# E1811SENSE_1.net
KiCad netlist of a schematic drawn in Altium Designer
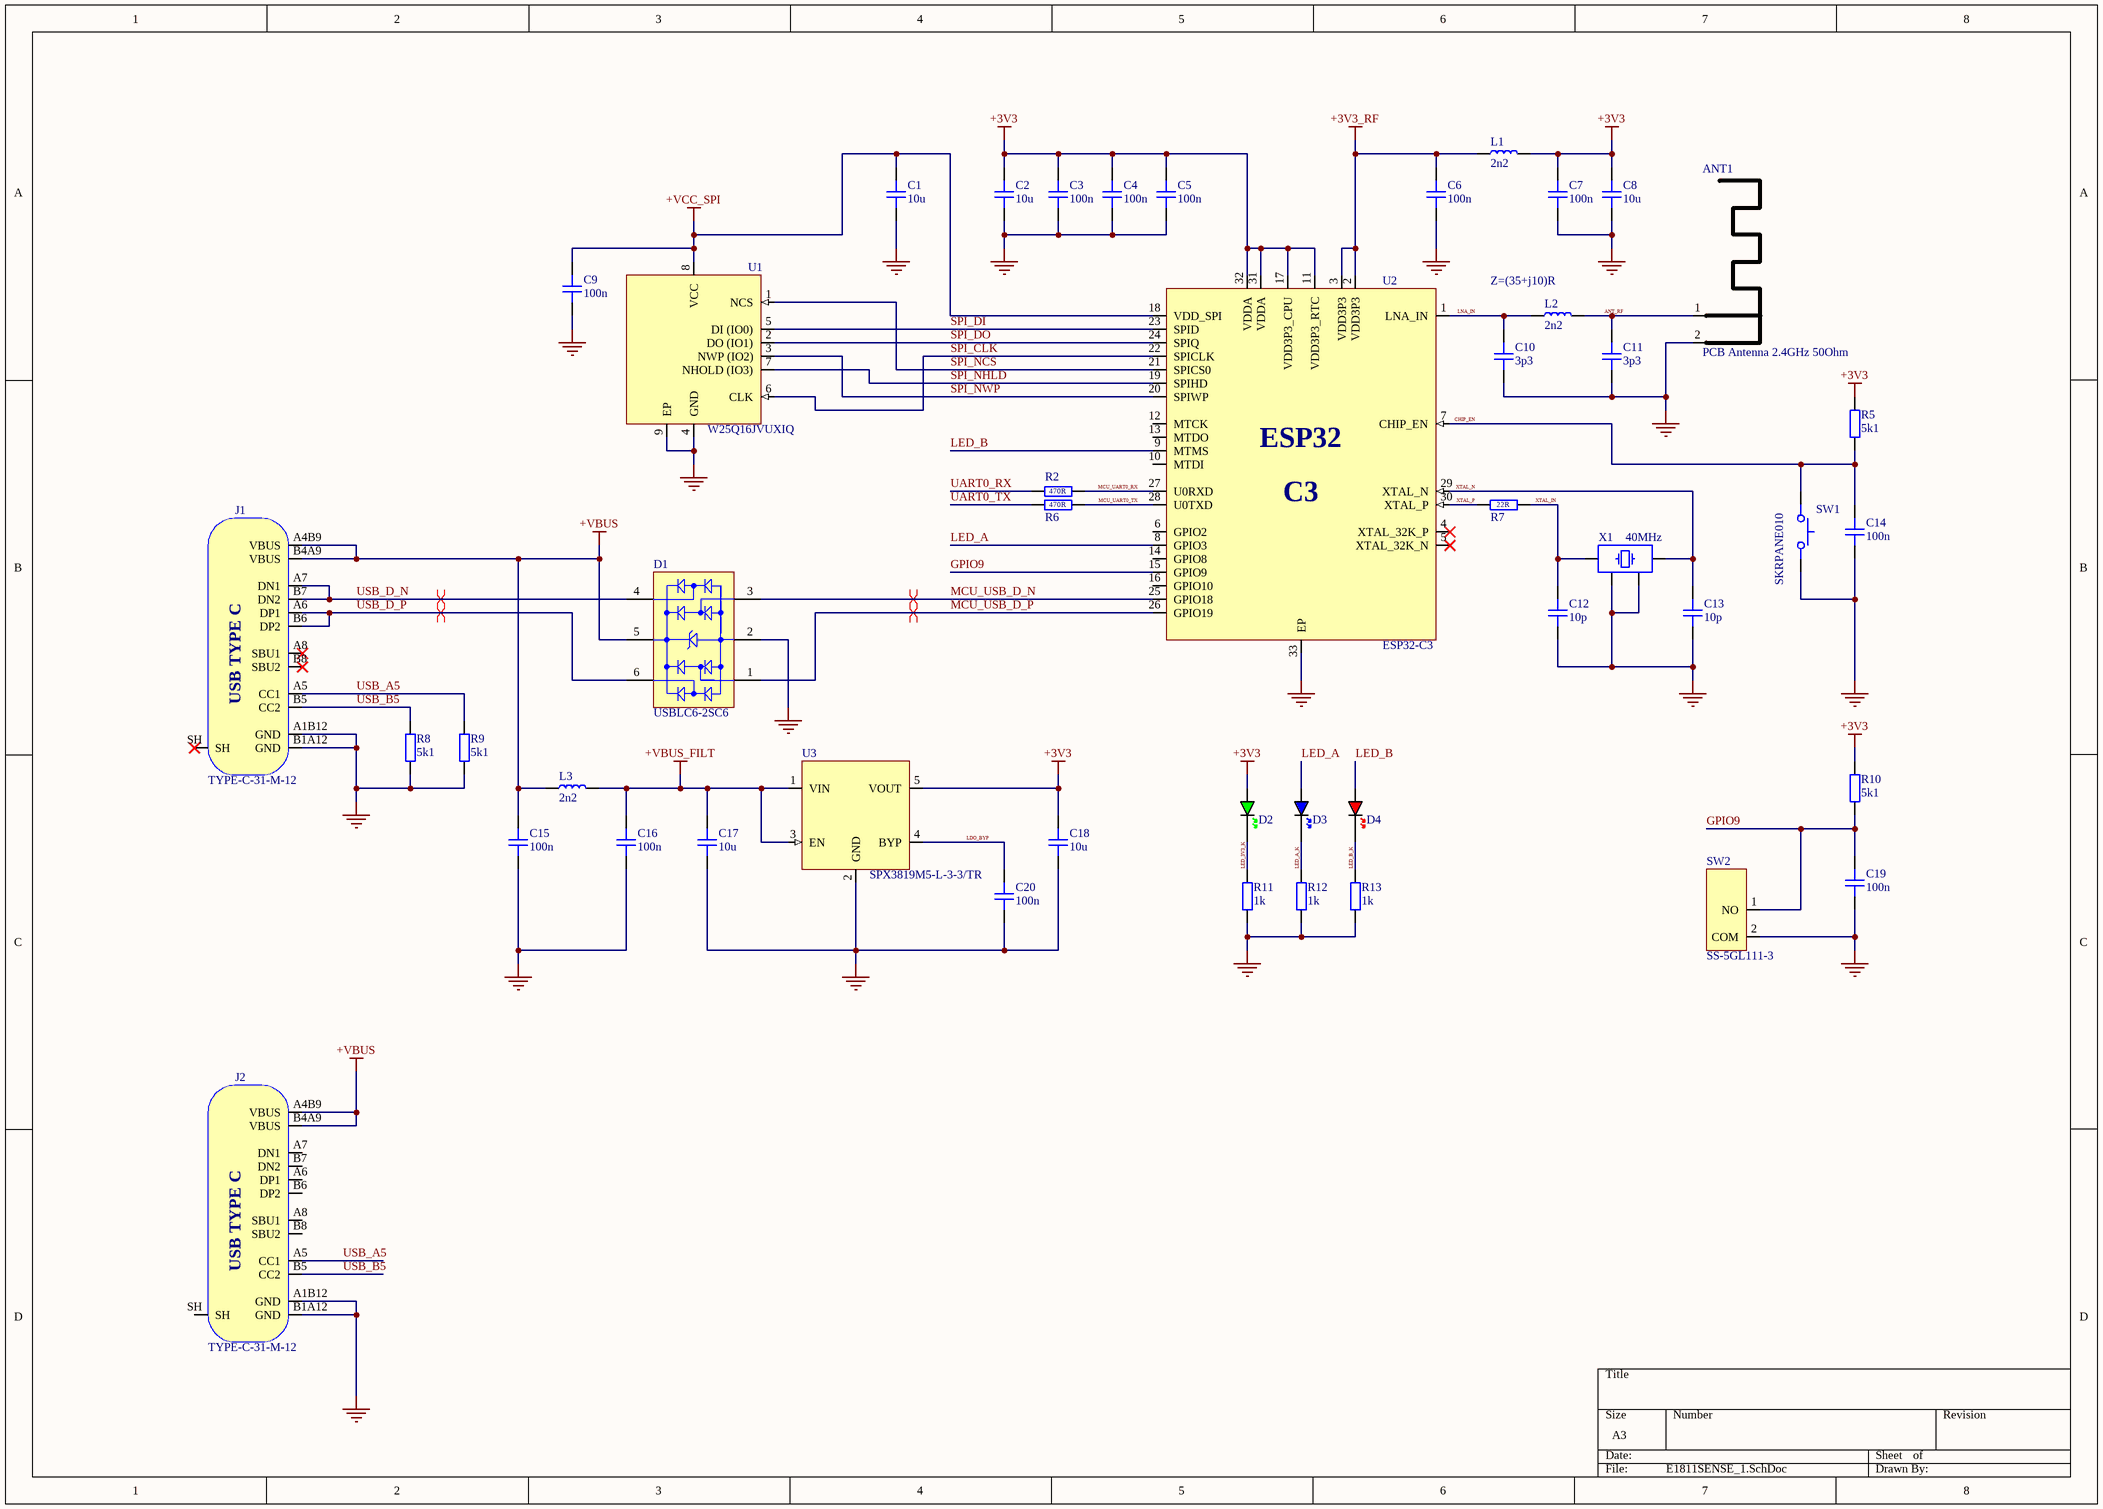
[diagram p0: E1811SENSE_1.SchDoc]

(export (version "E")
  (design (tool "Eeschema 10.0.6"))
  (components
    (comp (ref "ANT1")
      (value "PCB Antenna 2.4GHz 50Ohm")
      (footprint "ANT_IFA_USB_2_4GHZ_50R")
      (description "Inverted F 2.4GHz ISM PCB Antenna 50 Ohm")
      (libsource (lib "Schematic-Lib-PhilsLab") (part "ANT_IFA_USB_2_4GHZ_50R"))
    )
    (comp (ref "C1")
      (value "10u")
      (footprint "CAP_0603")
      (description "Capacitor SMD 0603 10V")
      (fields
        (field (name "MANUFACTURER") "Samsung")
        (field (name "MANUFACTURER PART NUMBER") "CL10A106KP8NNNC")
      )
      (libsource (lib "Schematic-Lib-PhilsLab") (part "CAP_0603_10V"))
    )
    (comp (ref "C2")
      (value "10u")
      (footprint "CAP_0603")
      (description "Capacitor SMD 0603 10V")
      (fields
        (field (name "MANUFACTURER") "Samsung")
        (field (name "MANUFACTURER PART NUMBER") "CL10A106KP8NNNC")
      )
      (libsource (lib "Schematic-Lib-PhilsLab") (part "CAP_0603_10V"))
    )
    (comp (ref "C3")
      (value "100n")
      (footprint "CAP_0402")
      (description "Capacitor SMD 0402 50V")
      (fields
        (field (name "MANUFACTURER") "Samsung")
        (field (name "MANUFACTURER PART NUMBER") "CL05B104KO5NNNC")
      )
      (libsource (lib "Schematic-Lib-PhilsLab") (part "CAP_0402_50V"))
    )
    (comp (ref "C4")
      (value "100n")
      (footprint "CAP_0402")
      (description "Capacitor SMD 0402 50V")
      (fields
        (field (name "MANUFACTURER") "Samsung")
        (field (name "MANUFACTURER PART NUMBER") "CL05B104KO5NNNC")
      )
      (libsource (lib "Schematic-Lib-PhilsLab") (part "CAP_0402_50V"))
    )
    (comp (ref "C5")
      (value "100n")
      (footprint "CAP_0402")
      (description "Capacitor SMD 0402 50V")
      (fields
        (field (name "MANUFACTURER") "Samsung")
        (field (name "MANUFACTURER PART NUMBER") "CL05B104KO5NNNC")
      )
      (libsource (lib "Schematic-Lib-PhilsLab") (part "CAP_0402_50V"))
    )
    (comp (ref "C6")
      (value "100n")
      (footprint "CAP_0402")
      (description "Capacitor SMD 0402 50V")
      (fields
        (field (name "MANUFACTURER") "Samsung")
        (field (name "MANUFACTURER PART NUMBER") "CL05B104KO5NNNC")
      )
      (libsource (lib "Schematic-Lib-PhilsLab") (part "CAP_0402_50V"))
    )
    (comp (ref "C7")
      (value "100n")
      (footprint "CAP_0402")
      (description "Capacitor SMD 0402 50V")
      (fields
        (field (name "MANUFACTURER") "Samsung")
        (field (name "MANUFACTURER PART NUMBER") "CL05B104KO5NNNC")
      )
      (libsource (lib "Schematic-Lib-PhilsLab") (part "CAP_0402_50V"))
    )
    (comp (ref "C8")
      (value "10u")
      (footprint "CAP_0603")
      (description "Capacitor SMD 0603 10V")
      (fields
        (field (name "MANUFACTURER") "Samsung")
        (field (name "MANUFACTURER PART NUMBER") "CL10A106KP8NNNC")
      )
      (libsource (lib "Schematic-Lib-PhilsLab") (part "CAP_0603_10V"))
    )
    (comp (ref "C9")
      (value "100n")
      (footprint "CAP_0402")
      (description "Capacitor SMD 0402 50V")
      (fields
        (field (name "MANUFACTURER") "Samsung")
        (field (name "MANUFACTURER PART NUMBER") "CL05B104KO5NNNC")
      )
      (libsource (lib "Schematic-Lib-PhilsLab") (part "CAP_0402_50V"))
    )
    (comp (ref "C10")
      (value "3p3")
      (footprint "CAP_0402")
      (description "Capacitor SMD 0402 50V")
      (fields (field (name "MANUFACTURER") "FH") (field (name "MANUFACTURER PART NUMBER") "0402CG3R3C500NT"))
      (libsource (lib "Schematic-Lib-PhilsLab") (part "CAP_0402_50V"))
    )
    (comp (ref "C11")
      (value "3p3")
      (footprint "CAP_0402")
      (description "Capacitor SMD 0402 50V")
      (fields (field (name "MANUFACTURER") "FH") (field (name "MANUFACTURER PART NUMBER") "0402CG3R3C500NT"))
      (libsource (lib "Schematic-Lib-PhilsLab") (part "CAP_0402_50V"))
    )
    (comp (ref "C12")
      (value "10p")
      (footprint "CAP_0402")
      (description "Capacitor SMD 0402 50V")
      (fields
        (field (name "MANUFACTURER") "Samsung")
        (field (name "MANUFACTURER PART NUMBER") "CL05C100JB5NNNC")
      )
      (libsource (lib "Schematic-Lib-PhilsLab") (part "CAP_0402_50V"))
    )
    (comp (ref "C13")
      (value "10p")
      (footprint "CAP_0402")
      (description "Capacitor SMD 0402 50V")
      (fields
        (field (name "MANUFACTURER") "Samsung")
        (field (name "MANUFACTURER PART NUMBER") "CL05C100JB5NNNC")
      )
      (libsource (lib "Schematic-Lib-PhilsLab") (part "CAP_0402_50V"))
    )
    (comp (ref "C14")
      (value "100n")
      (footprint "CAP_0402")
      (description "Capacitor SMD 0402 50V")
      (fields
        (field (name "MANUFACTURER") "Samsung")
        (field (name "MANUFACTURER PART NUMBER") "CL05B104KO5NNNC")
      )
      (libsource (lib "Schematic-Lib-PhilsLab") (part "CAP_0402_50V"))
    )
    (comp (ref "C15")
      (value "100n")
      (footprint "CAP_0402")
      (description "Capacitor SMD 0402 50V")
      (fields
        (field (name "MANUFACTURER") "Samsung")
        (field (name "MANUFACTURER PART NUMBER") "CL05B104KO5NNNC")
      )
      (libsource (lib "Schematic-Lib-PhilsLab") (part "CAP_0402_50V"))
    )
    (comp (ref "C16")
      (value "100n")
      (footprint "CAP_0402")
      (description "Capacitor SMD 0402 50V")
      (fields
        (field (name "MANUFACTURER") "Samsung")
        (field (name "MANUFACTURER PART NUMBER") "CL05B104KO5NNNC")
      )
      (libsource (lib "Schematic-Lib-PhilsLab") (part "CAP_0402_50V"))
    )
    (comp (ref "C17")
      (value "10u")
      (footprint "CAP_0603")
      (description "Capacitor SMD 0603 10V")
      (fields
        (field (name "MANUFACTURER") "Samsung")
        (field (name "MANUFACTURER PART NUMBER") "CL10A106KP8NNNC")
      )
      (libsource (lib "Schematic-Lib-PhilsLab") (part "CAP_0603_10V"))
    )
    (comp (ref "C18")
      (value "10u")
      (footprint "CAP_0603")
      (description "Capacitor SMD 0603 10V")
      (fields
        (field (name "MANUFACTURER") "Samsung")
        (field (name "MANUFACTURER PART NUMBER") "CL10A106KP8NNNC")
      )
      (libsource (lib "Schematic-Lib-PhilsLab") (part "CAP_0603_10V"))
    )
    (comp (ref "C19")
      (value "100n")
      (footprint "CAP_0402")
      (description "Capacitor SMD 0402 50V")
      (fields
        (field (name "MANUFACTURER") "Samsung")
        (field (name "MANUFACTURER PART NUMBER") "CL05B104KO5NNNC")
      )
      (libsource (lib "Schematic-Lib-PhilsLab") (part "CAP_0402_50V"))
    )
    (comp (ref "C20")
      (value "100n")
      (footprint "CAP_0402")
      (description "Capacitor SMD 0402 50V")
      (fields
        (field (name "MANUFACTURER") "Samsung")
        (field (name "MANUFACTURER PART NUMBER") "CL05B104KO5NNNC")
      )
      (libsource (lib "Schematic-Lib-PhilsLab") (part "CAP_0402_50V"))
    )
    (comp (ref "D1")
      (value "USBLC6-2SC6")
      (footprint "STM-SOT23-6L_V")
      (description "Very low capacitance ESD protection, 3.5 pF, -40 to 125 degC, 6-Pin SOT23, RoHS, Tape and Reel")
      (fields (field (name "MANUFACTURER") "STMicroelectronics"))
      (libsource (lib "Altium Content Vault") (part "STM-USB_DVI_HDMIULC6-4SC6X-SOT23-6L"))
    )
    (comp (ref "D2")
      (value "GREEN")
      (footprint "LED_0603_GREEN")
      (description "LED 0603 GREEN SMD")
      (libsource (lib "Schematic-Lib-PhilsLab") (part "LED_0603_GREEN"))
    )
    (comp (ref "D3")
      (value "BLUE")
      (footprint "LED_0603_BLUE")
      (description "LED 0603 BLUE SMD")
      (libsource (lib "Schematic-Lib-PhilsLab") (part "LED_0603_BLUE"))
    )
    (comp (ref "D4")
      (value "RED")
      (footprint "LED_0603_RED")
      (description "LED 0603 RED SMD")
      (libsource (lib "Schematic-Lib-PhilsLab") (part "LED_0603_RED"))
    )
    (comp (ref "J1")
      (value "TYPE-C-31-M-12")
      (footprint "TYPE-C-31-M-12")
      (description "USB Type C Connector Horizontal SMT")
      (fields (field (name "MANUFACTURER") "Koren Hroparts"))
      (libsource (lib "Schematic-Lib-PhilsLab") (part "TYPE-C-31-M-12"))
    )
    (comp (ref "J2")
      (value "TYPE-C-31-M-12")
      (footprint "TYPE-C-31-M-12")
      (description "USB Type C Connector Horizontal SMT")
      (fields (field (name "MANUFACTURER") "Koren Hroparts"))
      (libsource (lib "Schematic-Lib-PhilsLab") (part "TYPE-C-31-M-12"))
    )
    (comp (ref "L1")
      (value "2n2")
      (footprint "IND_0402")
      (description "Inductor SMD 0402")
      (fields
        (field (name "MANUFACTURER") "Murata")
        (field (name "MANUFACTURER PART NUMBER") "LQW15AN2N2G80D")
      )
      (libsource (lib "Schematic-Lib-PhilsLab") (part "IND_0402"))
    )
    (comp (ref "L2")
      (value "2n2")
      (footprint "IND_0402")
      (description "Inductor SMD 0402")
      (fields
        (field (name "MANUFACTURER") "Murata")
        (field (name "MANUFACTURER PART NUMBER") "LQW15AN2N2G80D")
      )
      (libsource (lib "Schematic-Lib-PhilsLab") (part "IND_0402"))
    )
    (comp (ref "L3")
      (value "2n2")
      (footprint "IND_0402")
      (description "Inductor SMD 0402")
      (fields
        (field (name "MANUFACTURER") "Murata")
        (field (name "MANUFACTURER PART NUMBER") "LQW15AN2N2G80D")
      )
      (libsource (lib "Schematic-Lib-PhilsLab") (part "IND_0402"))
    )
    (comp (ref "R2")
      (value "470R")
      (footprint "RES_0402")
      (description "Resistor SMD 0402")
      (fields
        (field (name "MANUFACTURER") "UNI-ROYAL")
        (field (name "MANUFACTURER PART NUMBER") "0402WGF4700TCE")
      )
      (libsource (lib "Schematic-Lib-PhilsLab") (part "RES_0402"))
    )
    (comp (ref "R5")
      (value "5k1")
      (footprint "RES_0402")
      (description "Resistor SMD 0402")
      (fields
        (field (name "MANUFACTURER") "YAGEO")
        (field (name "MANUFACTURER PART NUMBER") "RC0402JR-075K1L")
      )
      (libsource (lib "Schematic-Lib-PhilsLab") (part "RES_0402"))
    )
    (comp (ref "R6")
      (value "470R")
      (footprint "RES_0402")
      (description "Resistor SMD 0402")
      (fields
        (field (name "MANUFACTURER") "UNI-ROYAL")
        (field (name "MANUFACTURER PART NUMBER") "0402WGF4700TCE")
      )
      (libsource (lib "Schematic-Lib-PhilsLab") (part "RES_0402"))
    )
    (comp (ref "R7")
      (value "22R")
      (footprint "RES_0402")
      (description "Resistor SMD 0402")
      (fields
        (field (name "MANUFACTURER") "UNI-ROYAL")
        (field (name "MANUFACTURER PART NUMBER") "0402WGF220JTCE")
      )
      (libsource (lib "Schematic-Lib-PhilsLab") (part "RES_0402"))
    )
    (comp (ref "R8")
      (value "5k1")
      (footprint "RES_0402")
      (description "Resistor SMD 0402")
      (fields
        (field (name "MANUFACTURER") "YAGEO")
        (field (name "MANUFACTURER PART NUMBER") "RC0402JR-075K1L")
      )
      (libsource (lib "Schematic-Lib-PhilsLab") (part "RES_0402"))
    )
    (comp (ref "R9")
      (value "5k1")
      (footprint "RES_0402")
      (description "Resistor SMD 0402")
      (fields
        (field (name "MANUFACTURER") "YAGEO")
        (field (name "MANUFACTURER PART NUMBER") "RC0402JR-075K1L")
      )
      (libsource (lib "Schematic-Lib-PhilsLab") (part "RES_0402"))
    )
    (comp (ref "R10")
      (value "5k1")
      (footprint "RES_0402")
      (description "Resistor SMD 0402")
      (fields
        (field (name "MANUFACTURER") "YAGEO")
        (field (name "MANUFACTURER PART NUMBER") "RC0402JR-075K1L")
      )
      (libsource (lib "Schematic-Lib-PhilsLab") (part "RES_0402"))
    )
    (comp (ref "R11")
      (value "1k")
      (footprint "RES_0402")
      (description "Resistor SMD 0402")
      (fields
        (field (name "MANUFACTURER") "UNI-ROYAL")
        (field (name "MANUFACTURER PART NUMBER") "0402WGF4700TCE")
      )
      (libsource (lib "Schematic-Lib-PhilsLab") (part "RES_0402"))
    )
    (comp (ref "R12")
      (value "1k")
      (footprint "RES_0402")
      (description "Resistor SMD 0402")
      (fields
        (field (name "MANUFACTURER") "UNI-ROYAL")
        (field (name "MANUFACTURER PART NUMBER") "0402WGF4700TCE")
      )
      (libsource (lib "Schematic-Lib-PhilsLab") (part "RES_0402"))
    )
    (comp (ref "R13")
      (value "1k")
      (footprint "RES_0402")
      (description "Resistor SMD 0402")
      (fields
        (field (name "MANUFACTURER") "UNI-ROYAL")
        (field (name "MANUFACTURER PART NUMBER") "0402WGF4700TCE")
      )
      (libsource (lib "Schematic-Lib-PhilsLab") (part "RES_0402"))
    )
    (comp (ref "SW1")
      (value "SKRPANE010")
      (footprint "SKRPANE010")
      (description "Tactile Switch SMD SPST")
      (fields (field (name "MANUFACTURER") "Alps Alpine"))
      (libsource (lib "Schematic-Lib-PhilsLab") (part "SKRPANE010"))
    )
    (comp (ref "SW2")
      (value "SS-5GL111-3")
      (footprint "SS-5GL1131-3")
      (libsource (lib "SchLibrary") (part "SS-5GL111-3"))
    )
    (comp (ref "U1")
      (value "W25Q16JVUXIQ")
      (footprint "USON-8-2X3MM")
      (description "16M-BIT SERIAL FLASH MEMORY WITH\r\nDUAL/QUAD SPI USON-8")
      (fields (field (name "MANUFACTURER") "Winbond"))
      (libsource (lib "Schematic-Lib-PhilsLab") (part "W25Q16JVUXIQ"))
    )
    (comp (ref "U2")
      (value "ESP32-C3")
      (footprint "QFN32-5x5")
      (fields (field (name "MANUFACTURER") "Espressif"))
      (libsource (lib "Schematic-Lib-PhilsLab") (part "ESP32-C3"))
    )
    (comp (ref "U3")
      (value "SPX3819M5-L-3-3/TR")
      (footprint "SOT-23-5")
      (description "500mA +3.3V Low-Noise LDO Voltage Regulator")
      (fields (field (name "MANUFACTURER") "MaxLinear"))
      (libsource (lib "Schematic-Lib-PhilsLab") (part "SPX3819M5-L-3-3/TR"))
    )
    (comp (ref "X1")
      (value "40MHz")
      (footprint "XTAL_2520")
      (description "Crystal SMD 2520")
      (fields (field (name "MANUFACTURER") "Seiko Epson"))
      (libsource (lib "Schematic-Lib-PhilsLab") (part "XTAL_2520"))
    )
  )
  (nets
    (net (code "1") (name "+3V3") (class "Default")
      (node (ref "C18") (pin "2") (pinfunction "2_2") (pintype "passive"))
      (node (ref "C2") (pin "2") (pinfunction "2_2") (pintype "passive"))
      (node (ref "C3") (pin "2") (pinfunction "2_2") (pintype "passive"))
      (node (ref "C4") (pin "2") (pinfunction "2_2") (pintype "passive"))
      (node (ref "C5") (pin "2") (pinfunction "2_2") (pintype "passive"))
      (node (ref "C7") (pin "2") (pinfunction "2_2") (pintype "passive"))
      (node (ref "C8") (pin "2") (pinfunction "2_2") (pintype "passive"))
      (node (ref "D2") (pin "A") (pinfunction "A_A") (pintype "passive"))
      (node (ref "L1") (pin "1") (pinfunction "1_1") (pintype "passive"))
      (node (ref "R10") (pin "2") (pinfunction "2_2") (pintype "passive"))
      (node (ref "R5") (pin "2") (pinfunction "2_2") (pintype "passive"))
      (node (ref "U2") (pin "11") (pinfunction "VDD3P3_RTC_11") (pintype "power_in"))
      (node (ref "U2") (pin "17") (pinfunction "VDD3P3_CPU_17") (pintype "power_in"))
      (node (ref "U2") (pin "31") (pinfunction "VDDA_31") (pintype "power_in"))
      (node (ref "U2") (pin "32") (pinfunction "VDDA_32") (pintype "power_in"))
      (node (ref "U3") (pin "5") (pinfunction "VOUT_5") (pintype "power_in"))
    )
    (net (code "2") (name "+3V3_RF") (class "Default")
      (node (ref "C6") (pin "2") (pinfunction "2_2") (pintype "passive"))
      (node (ref "L1") (pin "2") (pinfunction "2_2") (pintype "passive"))
      (node (ref "U2") (pin "2") (pinfunction "VDD3P3_2") (pintype "power_in"))
      (node (ref "U2") (pin "3") (pinfunction "VDD3P3_3") (pintype "power_in"))
    )
    (net (code "3") (name "+VBUS") (class "Default")
      (node (ref "C15") (pin "2") (pinfunction "2_2") (pintype "passive"))
      (node (ref "D1") (pin "5") (pinfunction "VBUS_5") (pintype "passive"))
      (node (ref "J1") (pin "A4B9") (pinfunction "VBUS_A4B9") (pintype "power_in"))
      (node (ref "J1") (pin "B4A9") (pinfunction "VBUS_B4A9") (pintype "power_in"))
      (node (ref "J2") (pin "A4B9") (pinfunction "VBUS_A4B9") (pintype "power_in"))
      (node (ref "J2") (pin "B4A9") (pinfunction "VBUS_B4A9") (pintype "power_in"))
      (node (ref "L3") (pin "2") (pinfunction "2_2") (pintype "passive"))
    )
    (net (code "4") (name "+VBUS_FILT") (class "Default")
      (node (ref "C16") (pin "2") (pinfunction "2_2") (pintype "passive"))
      (node (ref "C17") (pin "2") (pinfunction "2_2") (pintype "passive"))
      (node (ref "L3") (pin "1") (pinfunction "1_1") (pintype "passive"))
      (node (ref "U3") (pin "1") (pinfunction "VIN_1") (pintype "power_in"))
      (node (ref "U3") (pin "3") (pinfunction "EN_3") (pintype "input"))
    )
    (net (code "5") (name "+VCC_SPI") (class "Default")
      (node (ref "C1") (pin "2") (pinfunction "2_2") (pintype "passive"))
      (node (ref "C9") (pin "2") (pinfunction "2_2") (pintype "passive"))
      (node (ref "U1") (pin "8") (pinfunction "VCC_8") (pintype "power_in"))
      (node (ref "U2") (pin "18") (pinfunction "VDD_SPI_18") (pintype "power_in"))
    )
    (net (code "6") (name "/ANT_RF") (class "Default")
      (node (ref "ANT1") (pin "1") (pinfunction "RF_1") (pintype "passive"))
      (node (ref "C11") (pin "2") (pinfunction "2_2") (pintype "passive"))
      (node (ref "L2") (pin "1") (pinfunction "1_1") (pintype "passive"))
    )
    (net (code "7") (name "/CHIP_EN") (class "Default")
      (node (ref "C14") (pin "2") (pinfunction "2_2") (pintype "passive"))
      (node (ref "R5") (pin "1") (pinfunction "1_1") (pintype "passive"))
      (node (ref "SW1") (pin "34") (pintype "passive"))
      (node (ref "U2") (pin "7") (pinfunction "CHIP_EN_7") (pintype "input"))
    )
    (net (code "8") (name "/GPIO9") (class "Default")
      (node (ref "C19") (pin "2") (pinfunction "2_2") (pintype "passive"))
      (node (ref "R10") (pin "1") (pinfunction "1_1") (pintype "passive"))
      (node (ref "SW2") (pin "1") (pinfunction "NO_1") (pintype "passive"))
      (node (ref "U2") (pin "15") (pinfunction "GPIO9_15") (pintype "bidirectional"))
    )
    (net (code "9") (name "/LDO_BYP") (class "Default")
      (node (ref "C20") (pin "2") (pinfunction "2_2") (pintype "passive"))
      (node (ref "U3") (pin "4") (pinfunction "BYP_4") (pintype "passive"))
    )
    (net (code "10") (name "/LED_3V3_K") (class "Default")
      (node (ref "D2") (pin "K") (pinfunction "K_K") (pintype "passive"))
      (node (ref "R11") (pin "2") (pinfunction "2_2") (pintype "passive"))
    )
    (net (code "11") (name "/LED_A") (class "Default")
      (node (ref "D3") (pin "A") (pinfunction "A_A") (pintype "passive"))
      (node (ref "U2") (pin "8") (pinfunction "GPIO3_8") (pintype "bidirectional"))
    )
    (net (code "12") (name "/LED_A_K") (class "Default")
      (node (ref "D3") (pin "K") (pinfunction "K_K") (pintype "passive"))
      (node (ref "R12") (pin "2") (pinfunction "2_2") (pintype "passive"))
    )
    (net (code "13") (name "/LED_B") (class "Default")
      (node (ref "D4") (pin "A") (pinfunction "A_A") (pintype "passive"))
      (node (ref "U2") (pin "9") (pinfunction "MTMS_9") (pintype "bidirectional"))
    )
    (net (code "14") (name "/LED_B_K") (class "Default")
      (node (ref "D4") (pin "K") (pinfunction "K_K") (pintype "passive"))
      (node (ref "R13") (pin "2") (pinfunction "2_2") (pintype "passive"))
    )
    (net (code "15") (name "/LNA_IN") (class "Default")
      (node (ref "C10") (pin "2") (pinfunction "2_2") (pintype "passive"))
      (node (ref "L2") (pin "2") (pinfunction "2_2") (pintype "passive"))
      (node (ref "U2") (pin "1") (pinfunction "LNA_IN_1") (pintype "bidirectional"))
    )
    (net (code "16") (name "/MCU_UART0_RX") (class "Default")
      (node (ref "R2") (pin "2") (pinfunction "2_2") (pintype "passive"))
      (node (ref "U2") (pin "27") (pinfunction "U0RXD_27") (pintype "bidirectional"))
    )
    (net (code "17") (name "/MCU_UART0_TX") (class "Default")
      (node (ref "R6") (pin "2") (pinfunction "2_2") (pintype "passive"))
      (node (ref "U2") (pin "28") (pinfunction "U0TXD_28") (pintype "bidirectional"))
    )
    (net (code "18") (name "/MCU_USB_D_N") (class "Default")
      (node (ref "D1") (pin "3") (pinfunction "I/O_2_3") (pintype "passive"))
      (node (ref "U2") (pin "25") (pinfunction "GPIO18_25") (pintype "bidirectional"))
    )
    (net (code "19") (name "/MCU_USB_D_P") (class "Default")
      (node (ref "D1") (pin "1") (pinfunction "I/O_1_1") (pintype "passive"))
      (node (ref "U2") (pin "26") (pinfunction "GPIO19_26") (pintype "bidirectional"))
    )
    (net (code "20") (name "/SPI_CLK") (class "Default")
      (node (ref "U1") (pin "6") (pinfunction "CLK_6") (pintype "input"))
      (node (ref "U2") (pin "22") (pinfunction "SPICLK_22") (pintype "bidirectional"))
    )
    (net (code "21") (name "/SPI_DI") (class "Default")
      (node (ref "U1") (pin "5") (pinfunction "DI_(IO0)_5") (pintype "bidirectional"))
      (node (ref "U2") (pin "23") (pinfunction "SPID_23") (pintype "bidirectional"))
    )
    (net (code "22") (name "/SPI_DO") (class "Default")
      (node (ref "U1") (pin "2") (pinfunction "DO_(IO1)_2") (pintype "bidirectional"))
      (node (ref "U2") (pin "24") (pinfunction "SPIQ_24") (pintype "bidirectional"))
    )
    (net (code "23") (name "/SPI_NCS") (class "Default")
      (node (ref "U1") (pin "1") (pinfunction "NCS_1") (pintype "input"))
      (node (ref "U2") (pin "21") (pinfunction "SPICS0_21") (pintype "bidirectional"))
    )
    (net (code "24") (name "/SPI_NHLD") (class "Default")
      (node (ref "U1") (pin "7") (pinfunction "NHOLD_(IO3)_7") (pintype "bidirectional"))
      (node (ref "U2") (pin "19") (pinfunction "SPIHD_19") (pintype "bidirectional"))
    )
    (net (code "25") (name "/SPI_NWP") (class "Default")
      (node (ref "U1") (pin "3") (pinfunction "NWP_(IO2)_3") (pintype "bidirectional"))
      (node (ref "U2") (pin "20") (pinfunction "SPIWP_20") (pintype "bidirectional"))
    )
    (net (code "26") (name "/UART0_RX") (class "Default")
      (node (ref "R2") (pin "1") (pinfunction "1_1") (pintype "passive"))
    )
    (net (code "27") (name "/UART0_TX") (class "Default")
      (node (ref "R6") (pin "1") (pinfunction "1_1") (pintype "passive"))
    )
    (net (code "28") (name "/USB_A5") (class "Default")
      (node (ref "J1") (pin "A5") (pinfunction "CC1_A5") (pintype "passive"))
      (node (ref "J2") (pin "A5") (pinfunction "CC1_A5") (pintype "passive"))
      (node (ref "R9") (pin "1") (pinfunction "1_1") (pintype "passive"))
    )
    (net (code "29") (name "/USB_B5") (class "Default")
      (node (ref "J1") (pin "B5") (pinfunction "CC2_B5") (pintype "tri_state"))
      (node (ref "J2") (pin "B5") (pinfunction "CC2_B5") (pintype "tri_state"))
      (node (ref "R8") (pin "1") (pinfunction "1_1") (pintype "passive"))
    )
    (net (code "30") (name "/USB_D_N") (class "Default")
      (node (ref "D1") (pin "4") (pinfunction "I/O_3_4") (pintype "passive"))
      (node (ref "J1") (pin "A7") (pinfunction "DN1_A7") (pintype "bidirectional"))
      (node (ref "J1") (pin "B7") (pinfunction "DN2_B7") (pintype "bidirectional"))
    )
    (net (code "31") (name "/USB_D_P") (class "Default")
      (node (ref "D1") (pin "6") (pinfunction "I/O_4_6") (pintype "passive"))
      (node (ref "J1") (pin "A6") (pinfunction "DP1_A6") (pintype "bidirectional"))
      (node (ref "J1") (pin "B6") (pinfunction "DP2_B6") (pintype "bidirectional"))
    )
    (net (code "32") (name "/XTAL_IN") (class "Default")
      (node (ref "C12") (pin "2") (pinfunction "2_2") (pintype "passive"))
      (node (ref "R7") (pin "2") (pinfunction "2_2") (pintype "passive"))
      (node (ref "X1") (pin "3") (pinfunction "3_3") (pintype "passive"))
    )
    (net (code "33") (name "/XTAL_N") (class "Default")
      (node (ref "C13") (pin "2") (pinfunction "2_2") (pintype "passive"))
      (node (ref "U2") (pin "29") (pinfunction "XTAL_N_29") (pintype "input"))
      (node (ref "X1") (pin "1") (pinfunction "1_1") (pintype "passive"))
    )
    (net (code "34") (name "/XTAL_P") (class "Default")
      (node (ref "R7") (pin "1") (pinfunction "1_1") (pintype "passive"))
      (node (ref "U2") (pin "30") (pinfunction "XTAL_P_30") (pintype "input"))
    )
    (net (code "35") (name "GND") (class "Default")
      (node (ref "ANT1") (pin "2") (pinfunction "GND_2") (pintype "passive"))
      (node (ref "C1") (pin "1") (pinfunction "1_1") (pintype "passive"))
      (node (ref "C10") (pin "1") (pinfunction "1_1") (pintype "passive"))
      (node (ref "C11") (pin "1") (pinfunction "1_1") (pintype "passive"))
      (node (ref "C12") (pin "1") (pinfunction "1_1") (pintype "passive"))
      (node (ref "C13") (pin "1") (pinfunction "1_1") (pintype "passive"))
      (node (ref "C14") (pin "1") (pinfunction "1_1") (pintype "passive"))
      (node (ref "C15") (pin "1") (pinfunction "1_1") (pintype "passive"))
      (node (ref "C16") (pin "1") (pinfunction "1_1") (pintype "passive"))
      (node (ref "C17") (pin "1") (pinfunction "1_1") (pintype "passive"))
      (node (ref "C18") (pin "1") (pinfunction "1_1") (pintype "passive"))
      (node (ref "C19") (pin "1") (pinfunction "1_1") (pintype "passive"))
      (node (ref "C2") (pin "1") (pinfunction "1_1") (pintype "passive"))
      (node (ref "C20") (pin "1") (pinfunction "1_1") (pintype "passive"))
      (node (ref "C3") (pin "1") (pinfunction "1_1") (pintype "passive"))
      (node (ref "C4") (pin "1") (pinfunction "1_1") (pintype "passive"))
      (node (ref "C5") (pin "1") (pinfunction "1_1") (pintype "passive"))
      (node (ref "C6") (pin "1") (pinfunction "1_1") (pintype "passive"))
      (node (ref "C7") (pin "1") (pinfunction "1_1") (pintype "passive"))
      (node (ref "C8") (pin "1") (pinfunction "1_1") (pintype "passive"))
      (node (ref "C9") (pin "1") (pinfunction "1_1") (pintype "passive"))
      (node (ref "D1") (pin "2") (pinfunction "GND_2") (pintype "passive"))
      (node (ref "J1") (pin "A1B12") (pinfunction "GND_A1B12") (pintype "power_in"))
      (node (ref "J1") (pin "B1A12") (pinfunction "GND_B1A12") (pintype "power_in"))
      (node (ref "J2") (pin "A1B12") (pinfunction "GND_A1B12") (pintype "power_in"))
      (node (ref "J2") (pin "B1A12") (pinfunction "GND_B1A12") (pintype "power_in"))
      (node (ref "R11") (pin "1") (pinfunction "1_1") (pintype "passive"))
      (node (ref "R12") (pin "1") (pinfunction "1_1") (pintype "passive"))
      (node (ref "R13") (pin "1") (pinfunction "1_1") (pintype "passive"))
      (node (ref "R8") (pin "2") (pinfunction "2_2") (pintype "passive"))
      (node (ref "R9") (pin "2") (pinfunction "2_2") (pintype "passive"))
      (node (ref "SW1") (pin "12") (pintype "passive"))
      (node (ref "SW2") (pin "2") (pinfunction "COM_2") (pintype "passive"))
      (node (ref "U1") (pin "4") (pinfunction "GND_4") (pintype "power_in"))
      (node (ref "U1") (pin "9") (pinfunction "EP_9") (pintype "power_in"))
      (node (ref "U2") (pin "33") (pinfunction "EP_33") (pintype "power_in"))
      (node (ref "U3") (pin "2") (pinfunction "GND_2") (pintype "power_in"))
      (node (ref "X1") (pin "2") (pinfunction "2_2") (pintype "passive"))
      (node (ref "X1") (pin "4") (pinfunction "4_4") (pintype "passive"))
    )
    (net (code "36") (name "unconnected-(J1-PadSH)") (class "Default")
      (node (ref "J1") (pin "SH") (pinfunction "SH_SH") (pintype "power_in+no_connect"))
    )
    (net (code "37") (name "unconnected-(J1-SBU1-PadA8)") (class "Default")
      (node (ref "J1") (pin "A8") (pinfunction "SBU1_A8") (pintype "bidirectional+no_connect"))
    )
    (net (code "38") (name "unconnected-(J1-SBU2-PadB8)") (class "Default")
      (node (ref "J1") (pin "B8") (pinfunction "SBU2_B8") (pintype "bidirectional+no_connect"))
    )
    (net (code "39") (name "unconnected-(J2-DN1-PadA7)") (class "Default")
      (node (ref "J2") (pin "A7") (pinfunction "DN1_A7") (pintype "bidirectional"))
    )
    (net (code "40") (name "unconnected-(J2-DN2-PadB7)") (class "Default")
      (node (ref "J2") (pin "B7") (pinfunction "DN2_B7") (pintype "bidirectional"))
    )
    (net (code "41") (name "unconnected-(J2-DP1-PadA6)") (class "Default")
      (node (ref "J2") (pin "A6") (pinfunction "DP1_A6") (pintype "bidirectional"))
    )
    (net (code "42") (name "unconnected-(J2-DP2-PadB6)") (class "Default")
      (node (ref "J2") (pin "B6") (pinfunction "DP2_B6") (pintype "bidirectional"))
    )
    (net (code "43") (name "unconnected-(J2-PadSH)") (class "Default")
      (node (ref "J2") (pin "SH") (pinfunction "SH_SH") (pintype "power_in"))
    )
    (net (code "44") (name "unconnected-(J2-SBU1-PadA8)") (class "Default")
      (node (ref "J2") (pin "A8") (pinfunction "SBU1_A8") (pintype "bidirectional"))
    )
    (net (code "45") (name "unconnected-(J2-SBU2-PadB8)") (class "Default")
      (node (ref "J2") (pin "B8") (pinfunction "SBU2_B8") (pintype "bidirectional"))
    )
    (net (code "46") (name "unconnected-(U2-GPIO2-Pad6)") (class "Default")
      (node (ref "U2") (pin "6") (pinfunction "GPIO2_6") (pintype "bidirectional"))
    )
    (net (code "47") (name "unconnected-(U2-GPIO8-Pad14)") (class "Default")
      (node (ref "U2") (pin "14") (pinfunction "GPIO8_14") (pintype "bidirectional"))
    )
    (net (code "48") (name "unconnected-(U2-GPIO10-Pad16)") (class "Default")
      (node (ref "U2") (pin "16") (pinfunction "GPIO10_16") (pintype "bidirectional"))
    )
    (net (code "49") (name "unconnected-(U2-MTCK-Pad12)") (class "Default")
      (node (ref "U2") (pin "12") (pinfunction "MTCK_12") (pintype "bidirectional"))
    )
    (net (code "50") (name "unconnected-(U2-MTDI-Pad10)") (class "Default")
      (node (ref "U2") (pin "10") (pinfunction "MTDI_10") (pintype "bidirectional"))
    )
    (net (code "51") (name "unconnected-(U2-MTDO-Pad13)") (class "Default")
      (node (ref "U2") (pin "13") (pinfunction "MTDO_13") (pintype "bidirectional"))
    )
    (net (code "52") (name "unconnected-(U2-XTAL_32K_N-Pad5)") (class "Default")
      (node (ref "U2") (pin "5") (pinfunction "XTAL_32K_N_5") (pintype "bidirectional+no_connect"))
    )
    (net (code "53") (name "unconnected-(U2-XTAL_32K_P-Pad4)") (class "Default")
      (node (ref "U2") (pin "4") (pinfunction "XTAL_32K_P_4") (pintype "bidirectional+no_connect"))
    )
  )
)
